# Frontboard.net
KiCad netlist of a schematic drawn in EAGLE
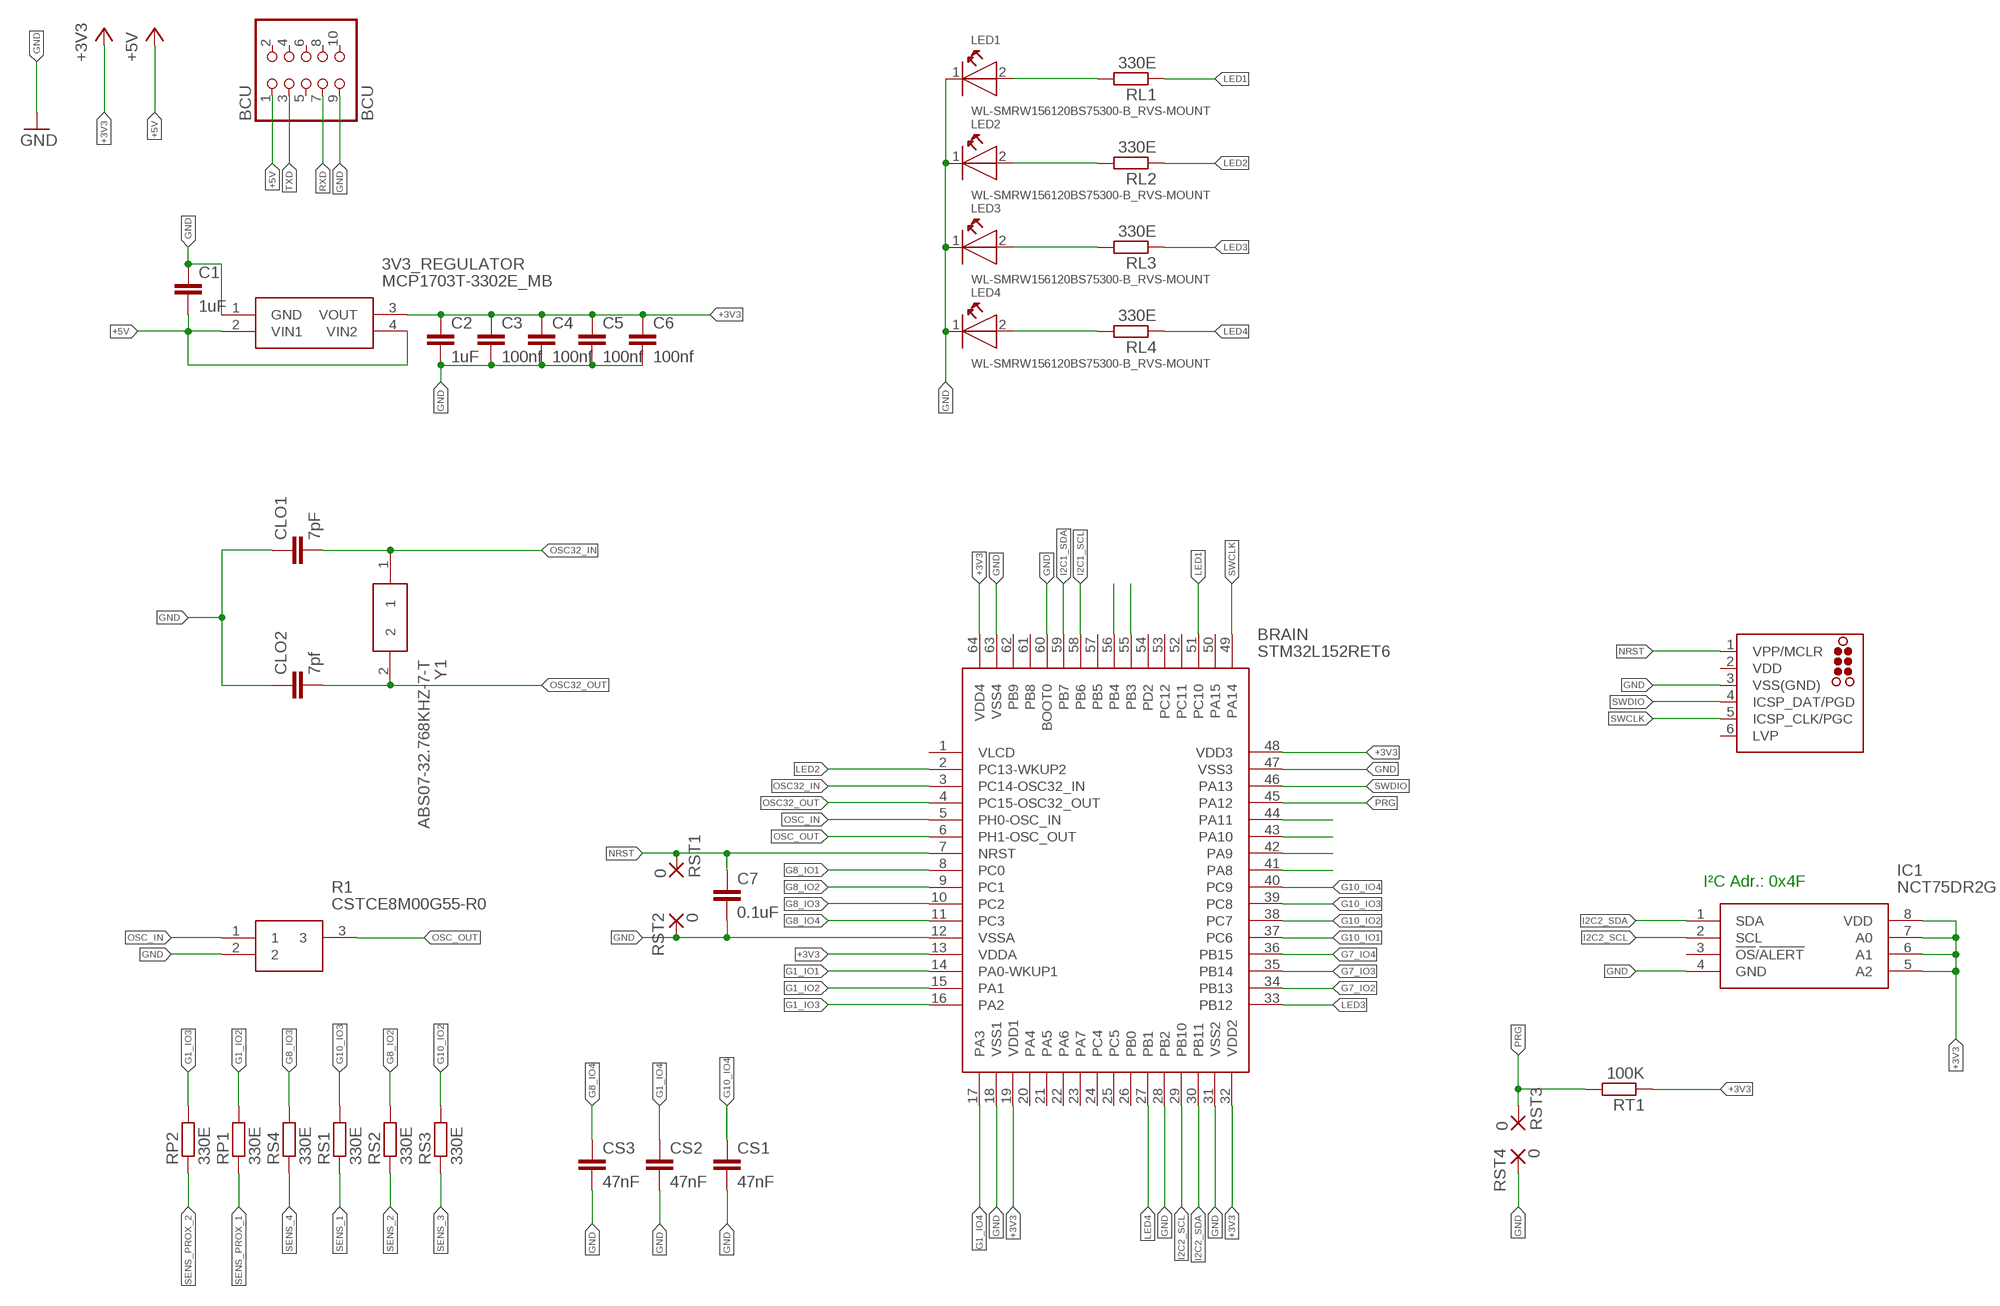
[diagram p0: schematic, sheet 1]

(export (version "E")
  (design (tool "Eeschema 10.0.6"))
  (components
    (comp (ref "3V3_REGULATOR")
      (value "MCP1703T-3302E_MB")
      (footprint "eagle-import:SOT-89(MB)")
      (fields
        (field (name "ARROW_PART_NUMBER") "MCP1703T-3302E/MB")
        (field (name "RS_PART_NUMBER") "9122916")
      )
      (libsource (lib "eagle-import") (part "MCP1703T-3302E_MB"))
    )
    (comp (ref "BCU")
      (value "BCU")
      (footprint "eagle-import:2X05SMD")
      (libsource (lib "eagle-import") (part "PINHD-2X5_2.54-SMD"))
    )
    (comp (ref "BRAIN")
      (value "STM32L152RET6")
      (footprint "eagle-import:QFP50P1200X1200X160-64N")
      (libsource (lib "eagle-import") (part "STM32L152RET6"))
    )
    (comp (ref "C1")
      (value "1uF")
      (footprint "eagle-import:C0603")
      (libsource (lib "eagle-import") (part "C-EUC0603"))
    )
    (comp (ref "C2")
      (value "1uF")
      (footprint "eagle-import:C0603")
      (libsource (lib "eagle-import") (part "C-EUC0603"))
    )
    (comp (ref "C3")
      (value "100nf")
      (footprint "eagle-import:C0603")
      (libsource (lib "eagle-import") (part "C-EUC0603"))
    )
    (comp (ref "C4")
      (value "100nf")
      (footprint "eagle-import:C0603")
      (libsource (lib "eagle-import") (part "C-EUC0603"))
    )
    (comp (ref "C5")
      (value "100nf")
      (footprint "eagle-import:C0603")
      (libsource (lib "eagle-import") (part "C-EUC0603"))
    )
    (comp (ref "C6")
      (value "100nf")
      (footprint "eagle-import:C0603")
      (libsource (lib "eagle-import") (part "C-EUC0603"))
    )
    (comp (ref "C7")
      (value "0.1uF")
      (footprint "eagle-import:C0603")
      (libsource (lib "eagle-import") (part "C-EUC0603"))
    )
    (comp (ref "CLO1")
      (value "7pF")
      (footprint "eagle-import:C0603")
      (libsource (lib "eagle-import") (part "C-EUC0603"))
    )
    (comp (ref "CLO2")
      (value "7pf")
      (footprint "eagle-import:C0603")
      (libsource (lib "eagle-import") (part "C-EUC0603"))
    )
    (comp (ref "CS1")
      (value "47nF")
      (footprint "eagle-import:C0603")
      (libsource (lib "eagle-import") (part "C-EUC0603"))
    )
    (comp (ref "CS2")
      (value "47nF")
      (footprint "eagle-import:C0603")
      (libsource (lib "eagle-import") (part "C-EUC0603"))
    )
    (comp (ref "CS3")
      (value "47nF")
      (footprint "eagle-import:C0603")
      (libsource (lib "eagle-import") (part "C-EUC0603"))
    )
    (comp (ref "IC1")
      (value "NCT75DR2G")
      (footprint "eagle-import:SOIC127P600X175-8N")
      (fields (field (name "RS_PART_NUMBER") "8051854P"))
      (libsource (lib "eagle-import") (part "NCT75DR2G"))
    )
    (comp (ref "LED1")
      (value "WL-SMRW156120BS75300-B_RVS-MOUNT")
      (footprint "eagle-import:WL-SMRW-1206-CYLDR-REVERSE-MOUNT")
      (libsource (lib "eagle-import") (part "WL-SMRW156120BS75300-B_RVS-MOUNT"))
    )
    (comp (ref "LED2")
      (value "WL-SMRW156120BS75300-B_RVS-MOUNT")
      (footprint "eagle-import:WL-SMRW-1206-CYLDR-REVERSE-MOUNT")
      (libsource (lib "eagle-import") (part "WL-SMRW156120BS75300-B_RVS-MOUNT"))
    )
    (comp (ref "LED3")
      (value "WL-SMRW156120BS75300-B_RVS-MOUNT")
      (footprint "eagle-import:WL-SMRW-1206-CYLDR-REVERSE-MOUNT")
      (libsource (lib "eagle-import") (part "WL-SMRW156120BS75300-B_RVS-MOUNT"))
    )
    (comp (ref "LED4")
      (value "WL-SMRW156120BS75300-B_RVS-MOUNT")
      (footprint "eagle-import:WL-SMRW-1206-CYLDR-REVERSE-MOUNT")
      (libsource (lib "eagle-import") (part "WL-SMRW156120BS75300-B_RVS-MOUNT"))
    )
    (comp (ref "R1")
      (value "CSTCE8M00G55-R0")
      (footprint "eagle-import:CSTCE12M0G55-R0")
      (fields (field (name "RS_PART_NUMBER") "7214821P"))
      (libsource (lib "eagle-import") (part "CSTCE8M00G55-R0"))
    )
    (comp (ref "RL1")
      (value "330E")
      (footprint "eagle-import:R0603")
      (libsource (lib "eagle-import") (part "R-EU_R0603"))
    )
    (comp (ref "RL2")
      (value "330E")
      (footprint "eagle-import:R0603")
      (libsource (lib "eagle-import") (part "R-EU_R0603"))
    )
    (comp (ref "RL3")
      (value "330E")
      (footprint "eagle-import:R0603")
      (libsource (lib "eagle-import") (part "R-EU_R0603"))
    )
    (comp (ref "RL4")
      (value "330E")
      (footprint "eagle-import:R0603")
      (libsource (lib "eagle-import") (part "R-EU_R0603"))
    )
    (comp (ref "RP1")
      (value "330E")
      (footprint "eagle-import:R0603")
      (libsource (lib "eagle-import") (part "R-EU_R0603"))
    )
    (comp (ref "RP2")
      (value "330E")
      (footprint "eagle-import:R0603")
      (libsource (lib "eagle-import") (part "R-EU_R0603"))
    )
    (comp (ref "RS1")
      (value "330E")
      (footprint "eagle-import:R0603")
      (libsource (lib "eagle-import") (part "R-EU_R0603"))
    )
    (comp (ref "RS2")
      (value "330E")
      (footprint "eagle-import:R0603")
      (libsource (lib "eagle-import") (part "R-EU_R0603"))
    )
    (comp (ref "RS3")
      (value "330E")
      (footprint "eagle-import:R0603")
      (libsource (lib "eagle-import") (part "R-EU_R0603"))
    )
    (comp (ref "RS4")
      (value "330E")
      (footprint "eagle-import:R0603")
      (libsource (lib "eagle-import") (part "R-EU_R0603"))
    )
    (comp (ref "RST1")
      (value "0")
      (footprint "eagle-import:SMD2,54-5,08")
      (libsource (lib "eagle-import") (part "SMD5"))
    )
    (comp (ref "RST2")
      (value "0")
      (footprint "eagle-import:SMD2,54-5,08")
      (libsource (lib "eagle-import") (part "SMD5"))
    )
    (comp (ref "RST3")
      (value "0")
      (footprint "eagle-import:SMD2,54-5,08")
      (libsource (lib "eagle-import") (part "SMD5"))
    )
    (comp (ref "RST4")
      (value "0")
      (footprint "eagle-import:SMD2,54-5,08")
      (libsource (lib "eagle-import") (part "SMD5"))
    )
    (comp (ref "RT1")
      (value "100K")
      (footprint "eagle-import:R0603")
      (libsource (lib "eagle-import") (part "R-EU_R0603"))
    )
    (comp (ref "SWD")
      (value "SWD")
      (footprint "eagle-import:TC2030-MCP-NL")
      (libsource (lib "eagle-import") (part "TC2030-MCP-NL"))
    )
    (comp (ref "Y1")
      (value "ABS07-32.768KHZ-7-T")
      (footprint "eagle-import:ABS-07")
      (fields (field (name "RS_PART_NUMBER") "1712773P"))
      (libsource (lib "eagle-import") (part "ABS07-32.768KHZ-7-T"))
    )
  )
  (nets
    (net (code "1") (name "+3V3") (class "Default")
      (node (ref "3V3_REGULATOR") (pin "3") (pinfunction "VOUT_3") (pintype "bidirectional"))
      (node (ref "BRAIN") (pin "13") (pinfunction "VDDA_13") (pintype "power_in"))
      (node (ref "BRAIN") (pin "19") (pinfunction "VDD1_19") (pintype "power_in"))
      (node (ref "BRAIN") (pin "32") (pinfunction "VDD2_32") (pintype "power_in"))
      (node (ref "BRAIN") (pin "48") (pinfunction "VDD3_48") (pintype "power_in"))
      (node (ref "BRAIN") (pin "64") (pinfunction "VDD4_64") (pintype "power_in"))
      (node (ref "C2") (pin "1") (pinfunction "1_1") (pintype "passive"))
      (node (ref "C3") (pin "1") (pinfunction "1_1") (pintype "passive"))
      (node (ref "C4") (pin "1") (pinfunction "1_1") (pintype "passive"))
      (node (ref "C5") (pin "1") (pinfunction "1_1") (pintype "passive"))
      (node (ref "C6") (pin "1") (pinfunction "1_1") (pintype "passive"))
      (node (ref "IC1") (pin "5") (pinfunction "A2_5") (pintype "bidirectional"))
      (node (ref "IC1") (pin "6") (pinfunction "A1_6") (pintype "bidirectional"))
      (node (ref "IC1") (pin "7") (pinfunction "A0_7") (pintype "bidirectional"))
      (node (ref "IC1") (pin "8") (pinfunction "VDD_8") (pintype "power_in"))
      (node (ref "RT1") (pin "1") (pinfunction "1_1") (pintype "passive"))
    )
    (net (code "2") (name "+5V") (class "Default")
      (node (ref "3V3_REGULATOR") (pin "2") (pinfunction "VIN1_2") (pintype "bidirectional"))
      (node (ref "3V3_REGULATOR") (pin "4") (pinfunction "VIN2_4") (pintype "bidirectional"))
      (node (ref "BCU") (pin "1") (pinfunction "1_1") (pintype "passive"))
      (node (ref "C1") (pin "2") (pinfunction "2_2") (pintype "passive"))
    )
    (net (code "3") (name "/VDD") (class "Default")
      (node (ref "SWD") (pin "2") (pinfunction "VDD_2") (pintype "power_in"))
    )
    (net (code "4") (name "/VLCD") (class "Default")
      (node (ref "BRAIN") (pin "1") (pinfunction "VLCD_1") (pintype "power_in"))
    )
    (net (code "5") (name "G1_IO1") (class "Default")
      (node (ref "BRAIN") (pin "14") (pinfunction "PA0-WKUP1_14") (pintype "bidirectional"))
    )
    (net (code "6") (name "G1_IO2") (class "Default")
      (node (ref "BRAIN") (pin "15") (pinfunction "PA1_15") (pintype "bidirectional"))
      (node (ref "RP1") (pin "2") (pinfunction "2_2") (pintype "passive"))
    )
    (net (code "7") (name "G1_IO3") (class "Default")
      (node (ref "BRAIN") (pin "16") (pinfunction "PA2_16") (pintype "bidirectional"))
      (node (ref "RP2") (pin "2") (pinfunction "2_2") (pintype "passive"))
    )
    (net (code "8") (name "G1_IO4") (class "Default")
      (node (ref "BRAIN") (pin "17") (pinfunction "PA3_17") (pintype "bidirectional"))
      (node (ref "CS2") (pin "1") (pinfunction "1_1") (pintype "passive"))
    )
    (net (code "9") (name "G7_IO2") (class "Default")
      (node (ref "BRAIN") (pin "34") (pinfunction "PB13_34") (pintype "bidirectional"))
    )
    (net (code "10") (name "G7_IO3") (class "Default")
      (node (ref "BRAIN") (pin "35") (pinfunction "PB14_35") (pintype "bidirectional"))
    )
    (net (code "11") (name "G7_IO4") (class "Default")
      (node (ref "BRAIN") (pin "36") (pinfunction "PB15_36") (pintype "bidirectional"))
    )
    (net (code "12") (name "G8_IO1") (class "Default")
      (node (ref "BRAIN") (pin "8") (pinfunction "PC0_8") (pintype "bidirectional"))
    )
    (net (code "13") (name "G8_IO2") (class "Default")
      (node (ref "BRAIN") (pin "9") (pinfunction "PC1_9") (pintype "bidirectional"))
      (node (ref "RS2") (pin "2") (pinfunction "2_2") (pintype "passive"))
    )
    (net (code "14") (name "G8_IO3") (class "Default")
      (node (ref "BRAIN") (pin "10") (pinfunction "PC2_10") (pintype "bidirectional"))
      (node (ref "RS4") (pin "2") (pinfunction "2_2") (pintype "passive"))
    )
    (net (code "15") (name "G8_IO4") (class "Default")
      (node (ref "BRAIN") (pin "11") (pinfunction "PC3_11") (pintype "bidirectional"))
      (node (ref "CS3") (pin "1") (pinfunction "1_1") (pintype "passive"))
    )
    (net (code "16") (name "G10_IO1") (class "Default")
      (node (ref "BRAIN") (pin "37") (pinfunction "PC6_37") (pintype "bidirectional"))
    )
    (net (code "17") (name "G10_IO2") (class "Default")
      (node (ref "BRAIN") (pin "38") (pinfunction "PC7_38") (pintype "bidirectional"))
      (node (ref "RS3") (pin "2") (pinfunction "2_2") (pintype "passive"))
    )
    (net (code "18") (name "G10_IO3") (class "Default")
      (node (ref "BRAIN") (pin "39") (pinfunction "PC8_39") (pintype "bidirectional"))
      (node (ref "RS1") (pin "2") (pinfunction "2_2") (pintype "passive"))
    )
    (net (code "19") (name "G10_IO4") (class "Default")
      (node (ref "BRAIN") (pin "40") (pinfunction "PC9_40") (pintype "bidirectional"))
      (node (ref "CS1") (pin "1") (pinfunction "1_1") (pintype "passive"))
    )
    (net (code "20") (name "GND") (class "Default")
      (node (ref "3V3_REGULATOR") (pin "1") (pinfunction "GND_1") (pintype "bidirectional"))
      (node (ref "BCU") (pin "9") (pinfunction "9_9") (pintype "passive"))
      (node (ref "BRAIN") (pin "12") (pinfunction "VSSA_12") (pintype "power_in"))
      (node (ref "BRAIN") (pin "18") (pinfunction "VSS1_18") (pintype "power_in"))
      (node (ref "BRAIN") (pin "28") (pinfunction "PB2_28") (pintype "bidirectional"))
      (node (ref "BRAIN") (pin "31") (pinfunction "VSS2_31") (pintype "power_in"))
      (node (ref "BRAIN") (pin "47") (pinfunction "VSS3_47") (pintype "power_in"))
      (node (ref "BRAIN") (pin "60") (pinfunction "BOOT0_60") (pintype "bidirectional"))
      (node (ref "BRAIN") (pin "63") (pinfunction "VSS4_63") (pintype "power_in"))
      (node (ref "C1") (pin "1") (pinfunction "1_1") (pintype "passive"))
      (node (ref "C2") (pin "2") (pinfunction "2_2") (pintype "passive"))
      (node (ref "C3") (pin "2") (pinfunction "2_2") (pintype "passive"))
      (node (ref "C4") (pin "2") (pinfunction "2_2") (pintype "passive"))
      (node (ref "C5") (pin "2") (pinfunction "2_2") (pintype "passive"))
      (node (ref "C6") (pin "2") (pinfunction "2_2") (pintype "passive"))
      (node (ref "C7") (pin "2") (pinfunction "2_2") (pintype "passive"))
      (node (ref "CLO1") (pin "1") (pinfunction "1_1") (pintype "passive"))
      (node (ref "CLO2") (pin "1") (pinfunction "1_1") (pintype "passive"))
      (node (ref "CS1") (pin "2") (pinfunction "2_2") (pintype "passive"))
      (node (ref "CS2") (pin "2") (pinfunction "2_2") (pintype "passive"))
      (node (ref "CS3") (pin "2") (pinfunction "2_2") (pintype "passive"))
      (node (ref "IC1") (pin "4") (pinfunction "GND_4") (pintype "power_in"))
      (node (ref "LED1") (pin "1") (pinfunction "K_1") (pintype "bidirectional"))
      (node (ref "LED2") (pin "1") (pinfunction "K_1") (pintype "bidirectional"))
      (node (ref "LED3") (pin "1") (pinfunction "K_1") (pintype "bidirectional"))
      (node (ref "LED4") (pin "1") (pinfunction "K_1") (pintype "bidirectional"))
      (node (ref "R1") (pin "2") (pinfunction "2_2") (pintype "bidirectional"))
      (node (ref "RST2") (pin "1") (pinfunction "P_1") (pintype "passive"))
      (node (ref "RST4") (pin "1") (pinfunction "P_1") (pintype "passive"))
      (node (ref "SWD") (pin "3") (pinfunction "VSS(GND)_3") (pintype "power_in"))
    )
    (net (code "21") (name "I2C1_SCL") (class "Default")
      (node (ref "BRAIN") (pin "58") (pinfunction "PB6_58") (pintype "bidirectional"))
    )
    (net (code "22") (name "I2C1_SDA") (class "Default")
      (node (ref "BRAIN") (pin "59") (pinfunction "PB7_59") (pintype "bidirectional"))
    )
    (net (code "23") (name "I2C2_SCL") (class "Default")
      (node (ref "BRAIN") (pin "29") (pinfunction "PB10_29") (pintype "bidirectional"))
      (node (ref "IC1") (pin "2") (pinfunction "SCL_2") (pintype "bidirectional"))
    )
    (net (code "24") (name "I2C2_SDA") (class "Default")
      (node (ref "BRAIN") (pin "30") (pinfunction "PB11_30") (pintype "bidirectional"))
      (node (ref "IC1") (pin "1") (pinfunction "SDA_1") (pintype "bidirectional"))
    )
    (net (code "25") (name "LED1") (class "Default")
      (node (ref "BRAIN") (pin "51") (pinfunction "PC10_51") (pintype "bidirectional"))
      (node (ref "RL1") (pin "1") (pinfunction "1_1") (pintype "passive"))
    )
    (net (code "26") (name "LED2") (class "Default")
      (node (ref "BRAIN") (pin "2") (pinfunction "PC13-WKUP2_2") (pintype "bidirectional"))
      (node (ref "RL2") (pin "1") (pinfunction "1_1") (pintype "passive"))
    )
    (net (code "27") (name "LED3") (class "Default")
      (node (ref "BRAIN") (pin "33") (pinfunction "PB12_33") (pintype "bidirectional"))
      (node (ref "RL3") (pin "1") (pinfunction "1_1") (pintype "passive"))
    )
    (net (code "28") (name "LED4") (class "Default")
      (node (ref "BRAIN") (pin "27") (pinfunction "PB1_27") (pintype "bidirectional"))
      (node (ref "RL4") (pin "1") (pinfunction "1_1") (pintype "passive"))
    )
    (net (code "29") (name "NRST") (class "Default")
      (node (ref "BRAIN") (pin "7") (pinfunction "NRST_7") (pintype "bidirectional"))
      (node (ref "C7") (pin "1") (pinfunction "1_1") (pintype "passive"))
      (node (ref "RST1") (pin "1") (pinfunction "P_1") (pintype "passive"))
      (node (ref "SWD") (pin "1") (pinfunction "VPP/MCLR_1") (pintype "passive"))
    )
    (net (code "30") (name "Net-(LED1-A)") (class "Default")
      (node (ref "LED1") (pin "2") (pinfunction "A_2") (pintype "bidirectional"))
      (node (ref "RL1") (pin "2") (pinfunction "2_2") (pintype "passive"))
    )
    (net (code "31") (name "Net-(LED2-A)") (class "Default")
      (node (ref "LED2") (pin "2") (pinfunction "A_2") (pintype "bidirectional"))
      (node (ref "RL2") (pin "2") (pinfunction "2_2") (pintype "passive"))
    )
    (net (code "32") (name "Net-(LED3-A)") (class "Default")
      (node (ref "LED3") (pin "2") (pinfunction "A_2") (pintype "bidirectional"))
      (node (ref "RL3") (pin "2") (pinfunction "2_2") (pintype "passive"))
    )
    (net (code "33") (name "Net-(LED4-A)") (class "Default")
      (node (ref "LED4") (pin "2") (pinfunction "A_2") (pintype "bidirectional"))
      (node (ref "RL4") (pin "2") (pinfunction "2_2") (pintype "passive"))
    )
    (net (code "34") (name "OSC32_IN") (class "Default")
      (node (ref "BRAIN") (pin "3") (pinfunction "PC14-OSC32_IN_3") (pintype "bidirectional"))
      (node (ref "CLO1") (pin "2") (pinfunction "2_2") (pintype "passive"))
      (node (ref "Y1") (pin "1") (pinfunction "1_1") (pintype "bidirectional"))
    )
    (net (code "35") (name "OSC32_OUT") (class "Default")
      (node (ref "BRAIN") (pin "4") (pinfunction "PC15-OSC32_OUT_4") (pintype "bidirectional"))
      (node (ref "CLO2") (pin "2") (pinfunction "2_2") (pintype "passive"))
      (node (ref "Y1") (pin "2") (pinfunction "2_2") (pintype "bidirectional"))
    )
    (net (code "36") (name "OSC_IN") (class "Default")
      (node (ref "BRAIN") (pin "5") (pinfunction "PH0-OSC_IN_5") (pintype "bidirectional"))
      (node (ref "R1") (pin "1") (pinfunction "1_1") (pintype "bidirectional"))
    )
    (net (code "37") (name "OSC_OUT") (class "Default")
      (node (ref "BRAIN") (pin "6") (pinfunction "PH1-OSC_OUT_6") (pintype "bidirectional"))
      (node (ref "R1") (pin "3") (pinfunction "3_3") (pintype "bidirectional"))
    )
    (net (code "38") (name "PRG") (class "Default")
      (node (ref "BRAIN") (pin "45") (pinfunction "PA12_45") (pintype "bidirectional"))
      (node (ref "RST3") (pin "1") (pinfunction "P_1") (pintype "passive"))
      (node (ref "RT1") (pin "2") (pinfunction "2_2") (pintype "passive"))
    )
    (net (code "39") (name "RXD") (class "Default")
      (node (ref "BCU") (pin "7") (pinfunction "7_7") (pintype "passive"))
    )
    (net (code "40") (name "SENS_1") (class "Default")
      (node (ref "RS1") (pin "1") (pinfunction "1_1") (pintype "passive"))
    )
    (net (code "41") (name "SENS_2") (class "Default")
      (node (ref "RS2") (pin "1") (pinfunction "1_1") (pintype "passive"))
    )
    (net (code "42") (name "SENS_3") (class "Default")
      (node (ref "RS3") (pin "1") (pinfunction "1_1") (pintype "passive"))
    )
    (net (code "43") (name "SENS_4") (class "Default")
      (node (ref "RS4") (pin "1") (pinfunction "1_1") (pintype "passive"))
    )
    (net (code "44") (name "SENS_PROX_1") (class "Default")
      (node (ref "RP1") (pin "1") (pinfunction "1_1") (pintype "passive"))
    )
    (net (code "45") (name "SENS_PROX_2") (class "Default")
      (node (ref "RP2") (pin "1") (pinfunction "1_1") (pintype "passive"))
    )
    (net (code "46") (name "SWCLK") (class "Default")
      (node (ref "BRAIN") (pin "49") (pinfunction "PA14_49") (pintype "bidirectional"))
      (node (ref "SWD") (pin "5") (pinfunction "ICSP_CLK/PGC_5") (pintype "output"))
    )
    (net (code "47") (name "SWDIO") (class "Default")
      (node (ref "BRAIN") (pin "46") (pinfunction "PA13_46") (pintype "bidirectional"))
      (node (ref "SWD") (pin "4") (pinfunction "ICSP_DAT/PGD_4") (pintype "bidirectional"))
    )
    (net (code "48") (name "TXD") (class "Default")
      (node (ref "BCU") (pin "3") (pinfunction "3_3") (pintype "passive"))
    )
    (net (code "49") (name "unconnected-(BCU-Pad2)") (class "Default")
      (node (ref "BCU") (pin "2") (pinfunction "2_2") (pintype "passive"))
    )
    (net (code "50") (name "unconnected-(BCU-Pad4)") (class "Default")
      (node (ref "BCU") (pin "4") (pinfunction "4_4") (pintype "passive"))
    )
    (net (code "51") (name "unconnected-(BCU-Pad5)") (class "Default")
      (node (ref "BCU") (pin "5") (pinfunction "5_5") (pintype "passive"))
    )
    (net (code "52") (name "unconnected-(BCU-Pad6)") (class "Default")
      (node (ref "BCU") (pin "6") (pinfunction "6_6") (pintype "passive"))
    )
    (net (code "53") (name "unconnected-(BCU-Pad8)") (class "Default")
      (node (ref "BCU") (pin "8") (pinfunction "8_8") (pintype "passive"))
    )
    (net (code "54") (name "unconnected-(BCU-Pad10)") (class "Default")
      (node (ref "BCU") (pin "10") (pinfunction "10_10") (pintype "passive"))
    )
    (net (code "55") (name "unconnected-(BRAIN-PA4-Pad20)") (class "Default")
      (node (ref "BRAIN") (pin "20") (pinfunction "PA4_20") (pintype "bidirectional"))
    )
    (net (code "56") (name "unconnected-(BRAIN-PA5-Pad21)") (class "Default")
      (node (ref "BRAIN") (pin "21") (pinfunction "PA5_21") (pintype "bidirectional"))
    )
    (net (code "57") (name "unconnected-(BRAIN-PA6-Pad22)") (class "Default")
      (node (ref "BRAIN") (pin "22") (pinfunction "PA6_22") (pintype "bidirectional"))
    )
    (net (code "58") (name "unconnected-(BRAIN-PA7-Pad23)") (class "Default")
      (node (ref "BRAIN") (pin "23") (pinfunction "PA7_23") (pintype "bidirectional"))
    )
    (net (code "59") (name "unconnected-(BRAIN-PA8-Pad41)") (class "Default")
      (node (ref "BRAIN") (pin "41") (pinfunction "PA8_41") (pintype "bidirectional"))
    )
    (net (code "60") (name "unconnected-(BRAIN-PA9-Pad42)") (class "Default")
      (node (ref "BRAIN") (pin "42") (pinfunction "PA9_42") (pintype "bidirectional"))
    )
    (net (code "61") (name "unconnected-(BRAIN-PA10-Pad43)") (class "Default")
      (node (ref "BRAIN") (pin "43") (pinfunction "PA10_43") (pintype "bidirectional"))
    )
    (net (code "62") (name "unconnected-(BRAIN-PA11-Pad44)") (class "Default")
      (node (ref "BRAIN") (pin "44") (pinfunction "PA11_44") (pintype "bidirectional"))
    )
    (net (code "63") (name "unconnected-(BRAIN-PA15-Pad50)") (class "Default")
      (node (ref "BRAIN") (pin "50") (pinfunction "PA15_50") (pintype "bidirectional"))
    )
    (net (code "64") (name "unconnected-(BRAIN-PB0-Pad26)") (class "Default")
      (node (ref "BRAIN") (pin "26") (pinfunction "PB0_26") (pintype "bidirectional"))
    )
    (net (code "65") (name "unconnected-(BRAIN-PB3-Pad55)") (class "Default")
      (node (ref "BRAIN") (pin "55") (pinfunction "PB3_55") (pintype "bidirectional"))
    )
    (net (code "66") (name "unconnected-(BRAIN-PB4-Pad56)") (class "Default")
      (node (ref "BRAIN") (pin "56") (pinfunction "PB4_56") (pintype "bidirectional"))
    )
    (net (code "67") (name "unconnected-(BRAIN-PB5-Pad57)") (class "Default")
      (node (ref "BRAIN") (pin "57") (pinfunction "PB5_57") (pintype "bidirectional"))
    )
    (net (code "68") (name "unconnected-(BRAIN-PB8-Pad61)") (class "Default")
      (node (ref "BRAIN") (pin "61") (pinfunction "PB8_61") (pintype "bidirectional"))
    )
    (net (code "69") (name "unconnected-(BRAIN-PB9-Pad62)") (class "Default")
      (node (ref "BRAIN") (pin "62") (pinfunction "PB9_62") (pintype "bidirectional"))
    )
    (net (code "70") (name "unconnected-(BRAIN-PC4-Pad24)") (class "Default")
      (node (ref "BRAIN") (pin "24") (pinfunction "PC4_24") (pintype "bidirectional"))
    )
    (net (code "71") (name "unconnected-(BRAIN-PC5-Pad25)") (class "Default")
      (node (ref "BRAIN") (pin "25") (pinfunction "PC5_25") (pintype "bidirectional"))
    )
    (net (code "72") (name "unconnected-(BRAIN-PC11-Pad52)") (class "Default")
      (node (ref "BRAIN") (pin "52") (pinfunction "PC11_52") (pintype "bidirectional"))
    )
    (net (code "73") (name "unconnected-(BRAIN-PC12-Pad53)") (class "Default")
      (node (ref "BRAIN") (pin "53") (pinfunction "PC12_53") (pintype "bidirectional"))
    )
    (net (code "74") (name "unconnected-(BRAIN-PD2-Pad54)") (class "Default")
      (node (ref "BRAIN") (pin "54") (pinfunction "PD2_54") (pintype "bidirectional"))
    )
    (net (code "75") (name "unconnected-(IC1-~{OS}{slash}~{ALERT}-Pad3)") (class "Default")
      (node (ref "IC1") (pin "3") (pinfunction "~{OS}/~{ALERT}_3") (pintype "bidirectional"))
    )
    (net (code "76") (name "unconnected-(SWD-LVP-Pad6)") (class "Default")
      (node (ref "SWD") (pin "6") (pinfunction "LVP_6") (pintype "bidirectional"))
    )
  )
)
